# Graphics_Card_Rev1.net
KiCad netlist of a schematic drawn in EAGLE
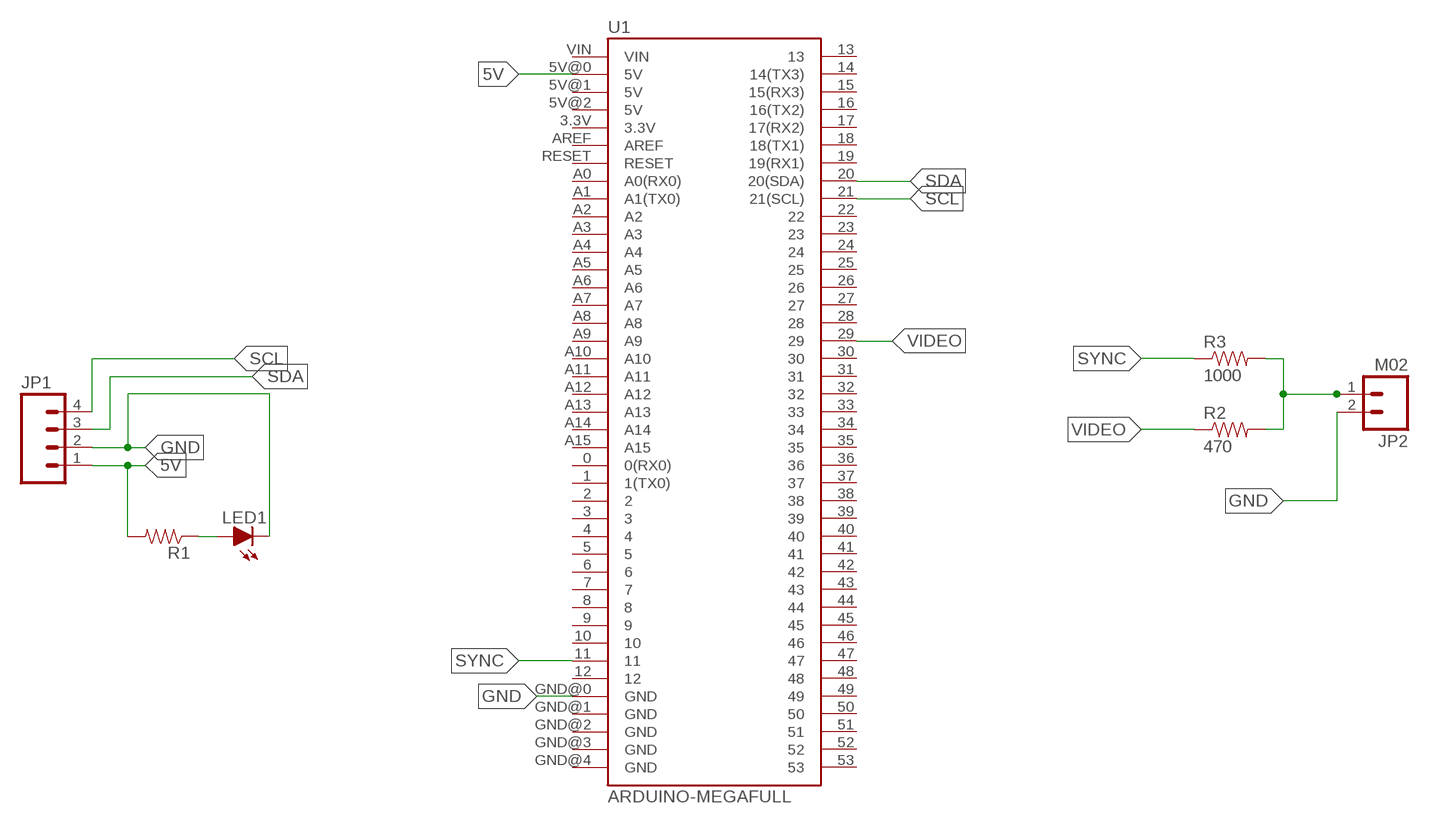
[diagram p0: schematic, sheet 1]

(export (version "E")
  (design (tool "Eeschema 10.0.6"))
  (components
    (comp (ref "JP1")
      (value "M04")
      (footprint "eagle-import:1X04")
      (libsource (lib "eagle-import") (part "M04"))
    )
    (comp (ref "JP2")
      (value "M02")
      (footprint "eagle-import:1X02")
      (libsource (lib "eagle-import") (part "M02"))
    )
    (comp (ref "LED1")
      (value "LED-5MM")
      (footprint "eagle-import:LED-5MM")
      (libsource (lib "eagle-import") (part "LED-5MM"))
    )
    (comp (ref "R1")
      (value "RESISTORPTH-1/2W")
      (footprint "eagle-import:AXIAL-0.5")
      (libsource (lib "eagle-import") (part "RESISTORPTH-1/2W"))
    )
    (comp (ref "R2")
      (value "470")
      (footprint "eagle-import:AXIAL-0.5")
      (libsource (lib "eagle-import") (part "RESISTORPTH-1/2W"))
    )
    (comp (ref "R3")
      (value "1000")
      (footprint "eagle-import:AXIAL-0.5")
      (libsource (lib "eagle-import") (part "RESISTORPTH-1/2W"))
    )
    (comp (ref "U1")
      (value "ARDUINO-MEGAFULL")
      (footprint "eagle-import:ARDUINO_MEGA")
      (libsource (lib "eagle-import") (part "ARDUINO-MEGAFULL"))
    )
  )
  (nets
    (net (code "1") (name "5V") (class "Default")
      (node (ref "JP1") (pin "1") (pinfunction "1_1") (pintype "passive"))
      (node (ref "R1") (pin "P$2") (pinfunction "2_P$2") (pintype "passive"))
      (node (ref "U1") (pin "5V@0") (pinfunction "5V_5V@0") (pintype "bidirectional"))
    )
    (net (code "2") (name "GND") (class "Default")
      (node (ref "JP1") (pin "2") (pinfunction "2_2") (pintype "passive"))
      (node (ref "JP2") (pin "2") (pinfunction "2_2") (pintype "passive"))
      (node (ref "LED1") (pin "K") (pinfunction "C_K") (pintype "passive"))
      (node (ref "U1") (pin "GND@0") (pinfunction "GND_GND@0") (pintype "bidirectional"))
    )
    (net (code "3") (name "Net-(R1-1)") (class "Default")
      (node (ref "LED1") (pin "A") (pinfunction "A_A") (pintype "passive"))
      (node (ref "R1") (pin "P$1") (pinfunction "1_P$1") (pintype "passive"))
    )
    (net (code "4") (name "Net-(R2-2)") (class "Default")
      (node (ref "JP2") (pin "1") (pinfunction "1_1") (pintype "passive"))
      (node (ref "R2") (pin "P$2") (pinfunction "2_P$2") (pintype "passive"))
      (node (ref "R3") (pin "P$2") (pinfunction "2_P$2") (pintype "passive"))
    )
    (net (code "5") (name "SCL") (class "Default")
      (node (ref "JP1") (pin "4") (pinfunction "4_4") (pintype "passive"))
      (node (ref "U1") (pin "21") (pinfunction "21(SCL)_21") (pintype "bidirectional"))
    )
    (net (code "6") (name "SDA") (class "Default")
      (node (ref "JP1") (pin "3") (pinfunction "3_3") (pintype "passive"))
      (node (ref "U1") (pin "20") (pinfunction "20(SDA)_20") (pintype "bidirectional"))
    )
    (net (code "7") (name "SYNC") (class "Default")
      (node (ref "R3") (pin "P$1") (pinfunction "1_P$1") (pintype "passive"))
      (node (ref "U1") (pin "11") (pinfunction "11_11") (pintype "bidirectional"))
    )
    (net (code "8") (name "VIDEO") (class "Default")
      (node (ref "R2") (pin "P$1") (pinfunction "1_P$1") (pintype "passive"))
      (node (ref "U1") (pin "29") (pinfunction "29_29") (pintype "bidirectional"))
    )
    (net (code "9") (name "unconnected-(U1-0(RX0)-Pad0)") (class "Default")
      (node (ref "U1") (pin "0") (pinfunction "0(RX0)_0") (pintype "bidirectional"))
    )
    (net (code "10") (name "unconnected-(U1-1(TX0)-Pad1)") (class "Default")
      (node (ref "U1") (pin "1") (pinfunction "1(TX0)_1") (pintype "bidirectional"))
    )
    (net (code "11") (name "unconnected-(U1-5V-Pad5V@1)") (class "Default")
      (node (ref "U1") (pin "5V@1") (pinfunction "5V_5V@1") (pintype "bidirectional"))
    )
    (net (code "12") (name "unconnected-(U1-5V-Pad5V@2)") (class "Default")
      (node (ref "U1") (pin "5V@2") (pinfunction "5V_5V@2") (pintype "bidirectional"))
    )
    (net (code "13") (name "unconnected-(U1-14(TX3)-Pad14)") (class "Default")
      (node (ref "U1") (pin "14") (pinfunction "14(TX3)_14") (pintype "bidirectional"))
    )
    (net (code "14") (name "unconnected-(U1-15(RX3)-Pad15)") (class "Default")
      (node (ref "U1") (pin "15") (pinfunction "15(RX3)_15") (pintype "bidirectional"))
    )
    (net (code "15") (name "unconnected-(U1-16(TX2)-Pad16)") (class "Default")
      (node (ref "U1") (pin "16") (pinfunction "16(TX2)_16") (pintype "bidirectional"))
    )
    (net (code "16") (name "unconnected-(U1-17(RX2)-Pad17)") (class "Default")
      (node (ref "U1") (pin "17") (pinfunction "17(RX2)_17") (pintype "bidirectional"))
    )
    (net (code "17") (name "unconnected-(U1-18(TX1)-Pad18)") (class "Default")
      (node (ref "U1") (pin "18") (pinfunction "18(TX1)_18") (pintype "bidirectional"))
    )
    (net (code "18") (name "unconnected-(U1-19(RX1)-Pad19)") (class "Default")
      (node (ref "U1") (pin "19") (pinfunction "19(RX1)_19") (pintype "bidirectional"))
    )
    (net (code "19") (name "unconnected-(U1-A0(RX0)-PadA0)") (class "Default")
      (node (ref "U1") (pin "A0") (pinfunction "A0(RX0)_A0") (pintype "bidirectional"))
    )
    (net (code "20") (name "unconnected-(U1-A1(TX0)-PadA1)") (class "Default")
      (node (ref "U1") (pin "A1") (pinfunction "A1(TX0)_A1") (pintype "bidirectional"))
    )
    (net (code "21") (name "unconnected-(U1-GND-PadGND@1)") (class "Default")
      (node (ref "U1") (pin "GND@1") (pinfunction "GND_GND@1") (pintype "bidirectional"))
    )
    (net (code "22") (name "unconnected-(U1-GND-PadGND@2)") (class "Default")
      (node (ref "U1") (pin "GND@2") (pinfunction "GND_GND@2") (pintype "bidirectional"))
    )
    (net (code "23") (name "unconnected-(U1-GND-PadGND@3)") (class "Default")
      (node (ref "U1") (pin "GND@3") (pinfunction "GND_GND@3") (pintype "bidirectional"))
    )
    (net (code "24") (name "unconnected-(U1-GND-PadGND@4)") (class "Default")
      (node (ref "U1") (pin "GND@4") (pinfunction "GND_GND@4") (pintype "bidirectional"))
    )
    (net (code "25") (name "unconnected-(U1-Pad2)") (class "Default")
      (node (ref "U1") (pin "2") (pinfunction "2_2") (pintype "bidirectional"))
    )
    (net (code "26") (name "unconnected-(U1-Pad3)") (class "Default")
      (node (ref "U1") (pin "3") (pinfunction "3_3") (pintype "bidirectional"))
    )
    (net (code "27") (name "unconnected-(U1-Pad3.3V)") (class "Default")
      (node (ref "U1") (pin "3.3V") (pinfunction "3.3V_3.3V") (pintype "bidirectional"))
    )
    (net (code "28") (name "unconnected-(U1-Pad4)") (class "Default")
      (node (ref "U1") (pin "4") (pinfunction "4_4") (pintype "bidirectional"))
    )
    (net (code "29") (name "unconnected-(U1-Pad5)") (class "Default")
      (node (ref "U1") (pin "5") (pinfunction "5_5") (pintype "bidirectional"))
    )
    (net (code "30") (name "unconnected-(U1-Pad6)") (class "Default")
      (node (ref "U1") (pin "6") (pinfunction "6_6") (pintype "bidirectional"))
    )
    (net (code "31") (name "unconnected-(U1-Pad7)") (class "Default")
      (node (ref "U1") (pin "7") (pinfunction "7_7") (pintype "bidirectional"))
    )
    (net (code "32") (name "unconnected-(U1-Pad8)") (class "Default")
      (node (ref "U1") (pin "8") (pinfunction "8_8") (pintype "bidirectional"))
    )
    (net (code "33") (name "unconnected-(U1-Pad9)") (class "Default")
      (node (ref "U1") (pin "9") (pinfunction "9_9") (pintype "bidirectional"))
    )
    (net (code "34") (name "unconnected-(U1-Pad10)") (class "Default")
      (node (ref "U1") (pin "10") (pinfunction "10_10") (pintype "bidirectional"))
    )
    (net (code "35") (name "unconnected-(U1-Pad12)") (class "Default")
      (node (ref "U1") (pin "12") (pinfunction "12_12") (pintype "bidirectional"))
    )
    (net (code "36") (name "unconnected-(U1-Pad13)") (class "Default")
      (node (ref "U1") (pin "13") (pinfunction "13_13") (pintype "bidirectional"))
    )
    (net (code "37") (name "unconnected-(U1-Pad22)") (class "Default")
      (node (ref "U1") (pin "22") (pinfunction "22_22") (pintype "bidirectional"))
    )
    (net (code "38") (name "unconnected-(U1-Pad23)") (class "Default")
      (node (ref "U1") (pin "23") (pinfunction "23_23") (pintype "bidirectional"))
    )
    (net (code "39") (name "unconnected-(U1-Pad24)") (class "Default")
      (node (ref "U1") (pin "24") (pinfunction "24_24") (pintype "bidirectional"))
    )
    (net (code "40") (name "unconnected-(U1-Pad25)") (class "Default")
      (node (ref "U1") (pin "25") (pinfunction "25_25") (pintype "bidirectional"))
    )
    (net (code "41") (name "unconnected-(U1-Pad26)") (class "Default")
      (node (ref "U1") (pin "26") (pinfunction "26_26") (pintype "bidirectional"))
    )
    (net (code "42") (name "unconnected-(U1-Pad27)") (class "Default")
      (node (ref "U1") (pin "27") (pinfunction "27_27") (pintype "bidirectional"))
    )
    (net (code "43") (name "unconnected-(U1-Pad28)") (class "Default")
      (node (ref "U1") (pin "28") (pinfunction "28_28") (pintype "bidirectional"))
    )
    (net (code "44") (name "unconnected-(U1-Pad30)") (class "Default")
      (node (ref "U1") (pin "30") (pinfunction "30_30") (pintype "bidirectional"))
    )
    (net (code "45") (name "unconnected-(U1-Pad31)") (class "Default")
      (node (ref "U1") (pin "31") (pinfunction "31_31") (pintype "bidirectional"))
    )
    (net (code "46") (name "unconnected-(U1-Pad32)") (class "Default")
      (node (ref "U1") (pin "32") (pinfunction "32_32") (pintype "bidirectional"))
    )
    (net (code "47") (name "unconnected-(U1-Pad33)") (class "Default")
      (node (ref "U1") (pin "33") (pinfunction "33_33") (pintype "bidirectional"))
    )
    (net (code "48") (name "unconnected-(U1-Pad34)") (class "Default")
      (node (ref "U1") (pin "34") (pinfunction "34_34") (pintype "bidirectional"))
    )
    (net (code "49") (name "unconnected-(U1-Pad35)") (class "Default")
      (node (ref "U1") (pin "35") (pinfunction "35_35") (pintype "bidirectional"))
    )
    (net (code "50") (name "unconnected-(U1-Pad36)") (class "Default")
      (node (ref "U1") (pin "36") (pinfunction "36_36") (pintype "bidirectional"))
    )
    (net (code "51") (name "unconnected-(U1-Pad37)") (class "Default")
      (node (ref "U1") (pin "37") (pinfunction "37_37") (pintype "bidirectional"))
    )
    (net (code "52") (name "unconnected-(U1-Pad38)") (class "Default")
      (node (ref "U1") (pin "38") (pinfunction "38_38") (pintype "bidirectional"))
    )
    (net (code "53") (name "unconnected-(U1-Pad39)") (class "Default")
      (node (ref "U1") (pin "39") (pinfunction "39_39") (pintype "bidirectional"))
    )
    (net (code "54") (name "unconnected-(U1-Pad40)") (class "Default")
      (node (ref "U1") (pin "40") (pinfunction "40_40") (pintype "bidirectional"))
    )
    (net (code "55") (name "unconnected-(U1-Pad41)") (class "Default")
      (node (ref "U1") (pin "41") (pinfunction "41_41") (pintype "bidirectional"))
    )
    (net (code "56") (name "unconnected-(U1-Pad42)") (class "Default")
      (node (ref "U1") (pin "42") (pinfunction "42_42") (pintype "bidirectional"))
    )
    (net (code "57") (name "unconnected-(U1-Pad43)") (class "Default")
      (node (ref "U1") (pin "43") (pinfunction "43_43") (pintype "bidirectional"))
    )
    (net (code "58") (name "unconnected-(U1-Pad44)") (class "Default")
      (node (ref "U1") (pin "44") (pinfunction "44_44") (pintype "bidirectional"))
    )
    (net (code "59") (name "unconnected-(U1-Pad45)") (class "Default")
      (node (ref "U1") (pin "45") (pinfunction "45_45") (pintype "bidirectional"))
    )
    (net (code "60") (name "unconnected-(U1-Pad46)") (class "Default")
      (node (ref "U1") (pin "46") (pinfunction "46_46") (pintype "bidirectional"))
    )
    (net (code "61") (name "unconnected-(U1-Pad47)") (class "Default")
      (node (ref "U1") (pin "47") (pinfunction "47_47") (pintype "bidirectional"))
    )
    (net (code "62") (name "unconnected-(U1-Pad48)") (class "Default")
      (node (ref "U1") (pin "48") (pinfunction "48_48") (pintype "bidirectional"))
    )
    (net (code "63") (name "unconnected-(U1-Pad49)") (class "Default")
      (node (ref "U1") (pin "49") (pinfunction "49_49") (pintype "bidirectional"))
    )
    (net (code "64") (name "unconnected-(U1-Pad50)") (class "Default")
      (node (ref "U1") (pin "50") (pinfunction "50_50") (pintype "bidirectional"))
    )
    (net (code "65") (name "unconnected-(U1-Pad51)") (class "Default")
      (node (ref "U1") (pin "51") (pinfunction "51_51") (pintype "bidirectional"))
    )
    (net (code "66") (name "unconnected-(U1-Pad52)") (class "Default")
      (node (ref "U1") (pin "52") (pinfunction "52_52") (pintype "bidirectional"))
    )
    (net (code "67") (name "unconnected-(U1-Pad53)") (class "Default")
      (node (ref "U1") (pin "53") (pinfunction "53_53") (pintype "bidirectional"))
    )
    (net (code "68") (name "unconnected-(U1-PadA2)") (class "Default")
      (node (ref "U1") (pin "A2") (pinfunction "A2_A2") (pintype "bidirectional"))
    )
    (net (code "69") (name "unconnected-(U1-PadA3)") (class "Default")
      (node (ref "U1") (pin "A3") (pinfunction "A3_A3") (pintype "bidirectional"))
    )
    (net (code "70") (name "unconnected-(U1-PadA4)") (class "Default")
      (node (ref "U1") (pin "A4") (pinfunction "A4_A4") (pintype "bidirectional"))
    )
    (net (code "71") (name "unconnected-(U1-PadA5)") (class "Default")
      (node (ref "U1") (pin "A5") (pinfunction "A5_A5") (pintype "bidirectional"))
    )
    (net (code "72") (name "unconnected-(U1-PadA6)") (class "Default")
      (node (ref "U1") (pin "A6") (pinfunction "A6_A6") (pintype "bidirectional"))
    )
    (net (code "73") (name "unconnected-(U1-PadA7)") (class "Default")
      (node (ref "U1") (pin "A7") (pinfunction "A7_A7") (pintype "bidirectional"))
    )
    (net (code "74") (name "unconnected-(U1-PadA8)") (class "Default")
      (node (ref "U1") (pin "A8") (pinfunction "A8_A8") (pintype "bidirectional"))
    )
    (net (code "75") (name "unconnected-(U1-PadA9)") (class "Default")
      (node (ref "U1") (pin "A9") (pinfunction "A9_A9") (pintype "bidirectional"))
    )
    (net (code "76") (name "unconnected-(U1-PadA10)") (class "Default")
      (node (ref "U1") (pin "A10") (pinfunction "A10_A10") (pintype "bidirectional"))
    )
    (net (code "77") (name "unconnected-(U1-PadA11)") (class "Default")
      (node (ref "U1") (pin "A11") (pinfunction "A11_A11") (pintype "bidirectional"))
    )
    (net (code "78") (name "unconnected-(U1-PadA12)") (class "Default")
      (node (ref "U1") (pin "A12") (pinfunction "A12_A12") (pintype "bidirectional"))
    )
    (net (code "79") (name "unconnected-(U1-PadA13)") (class "Default")
      (node (ref "U1") (pin "A13") (pinfunction "A13_A13") (pintype "bidirectional"))
    )
    (net (code "80") (name "unconnected-(U1-PadA14)") (class "Default")
      (node (ref "U1") (pin "A14") (pinfunction "A14_A14") (pintype "bidirectional"))
    )
    (net (code "81") (name "unconnected-(U1-PadA15)") (class "Default")
      (node (ref "U1") (pin "A15") (pinfunction "A15_A15") (pintype "bidirectional"))
    )
    (net (code "82") (name "unconnected-(U1-PadAREF)") (class "Default")
      (node (ref "U1") (pin "AREF") (pinfunction "AREF_AREF") (pintype "bidirectional"))
    )
    (net (code "83") (name "unconnected-(U1-PadRESET)") (class "Default")
      (node (ref "U1") (pin "RESET") (pinfunction "RESET_RESET") (pintype "bidirectional"))
    )
    (net (code "84") (name "unconnected-(U1-PadVIN)") (class "Default")
      (node (ref "U1") (pin "VIN") (pinfunction "VIN_VIN") (pintype "bidirectional"))
    )
  )
)
